# actuatorboard.net
KiCad netlist of a schematic drawn in EAGLE
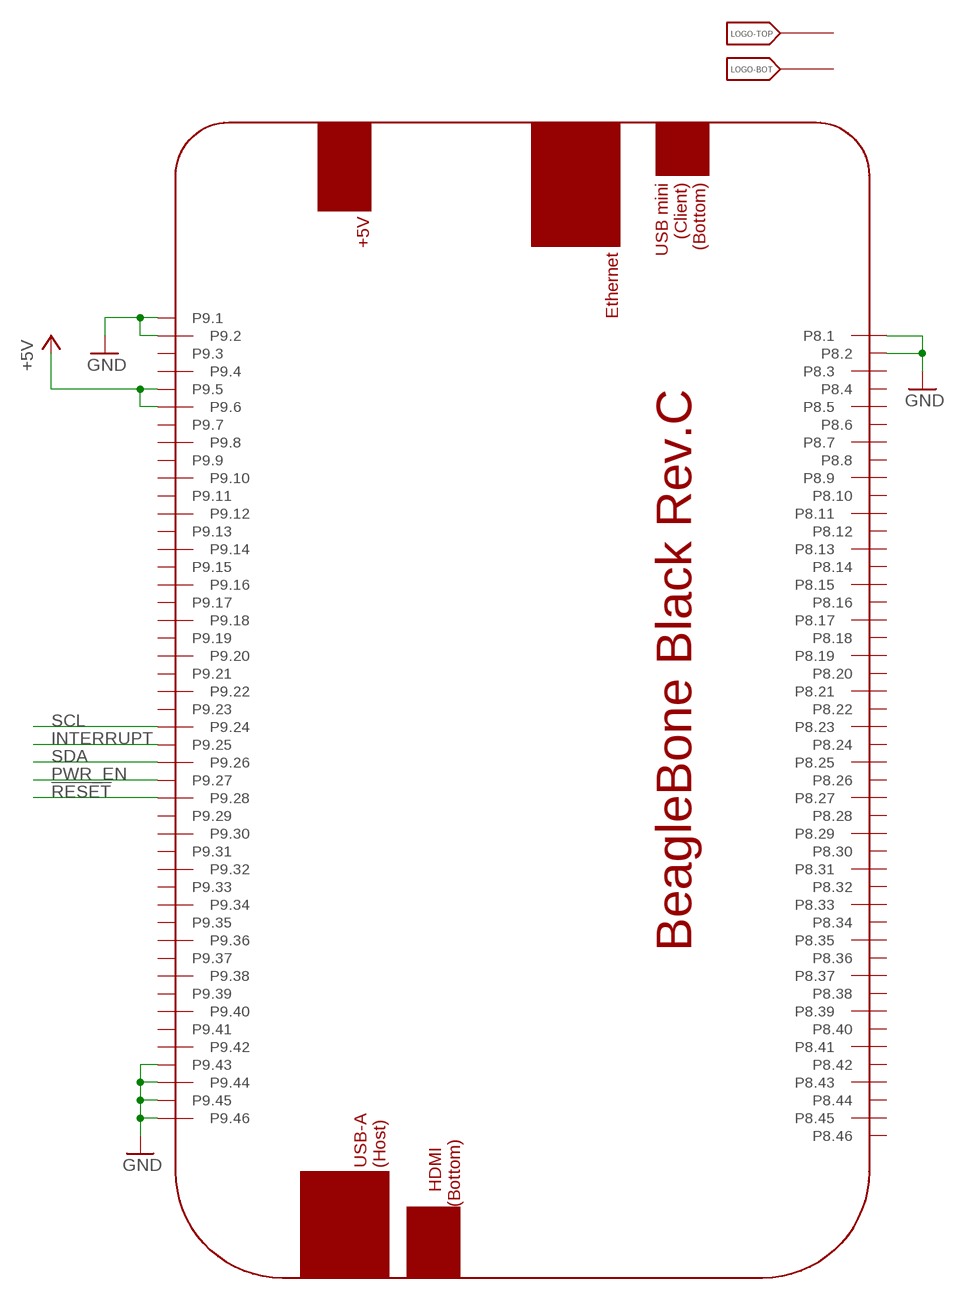
[diagram p0: schematic, sheet 1, part 1 of 2]
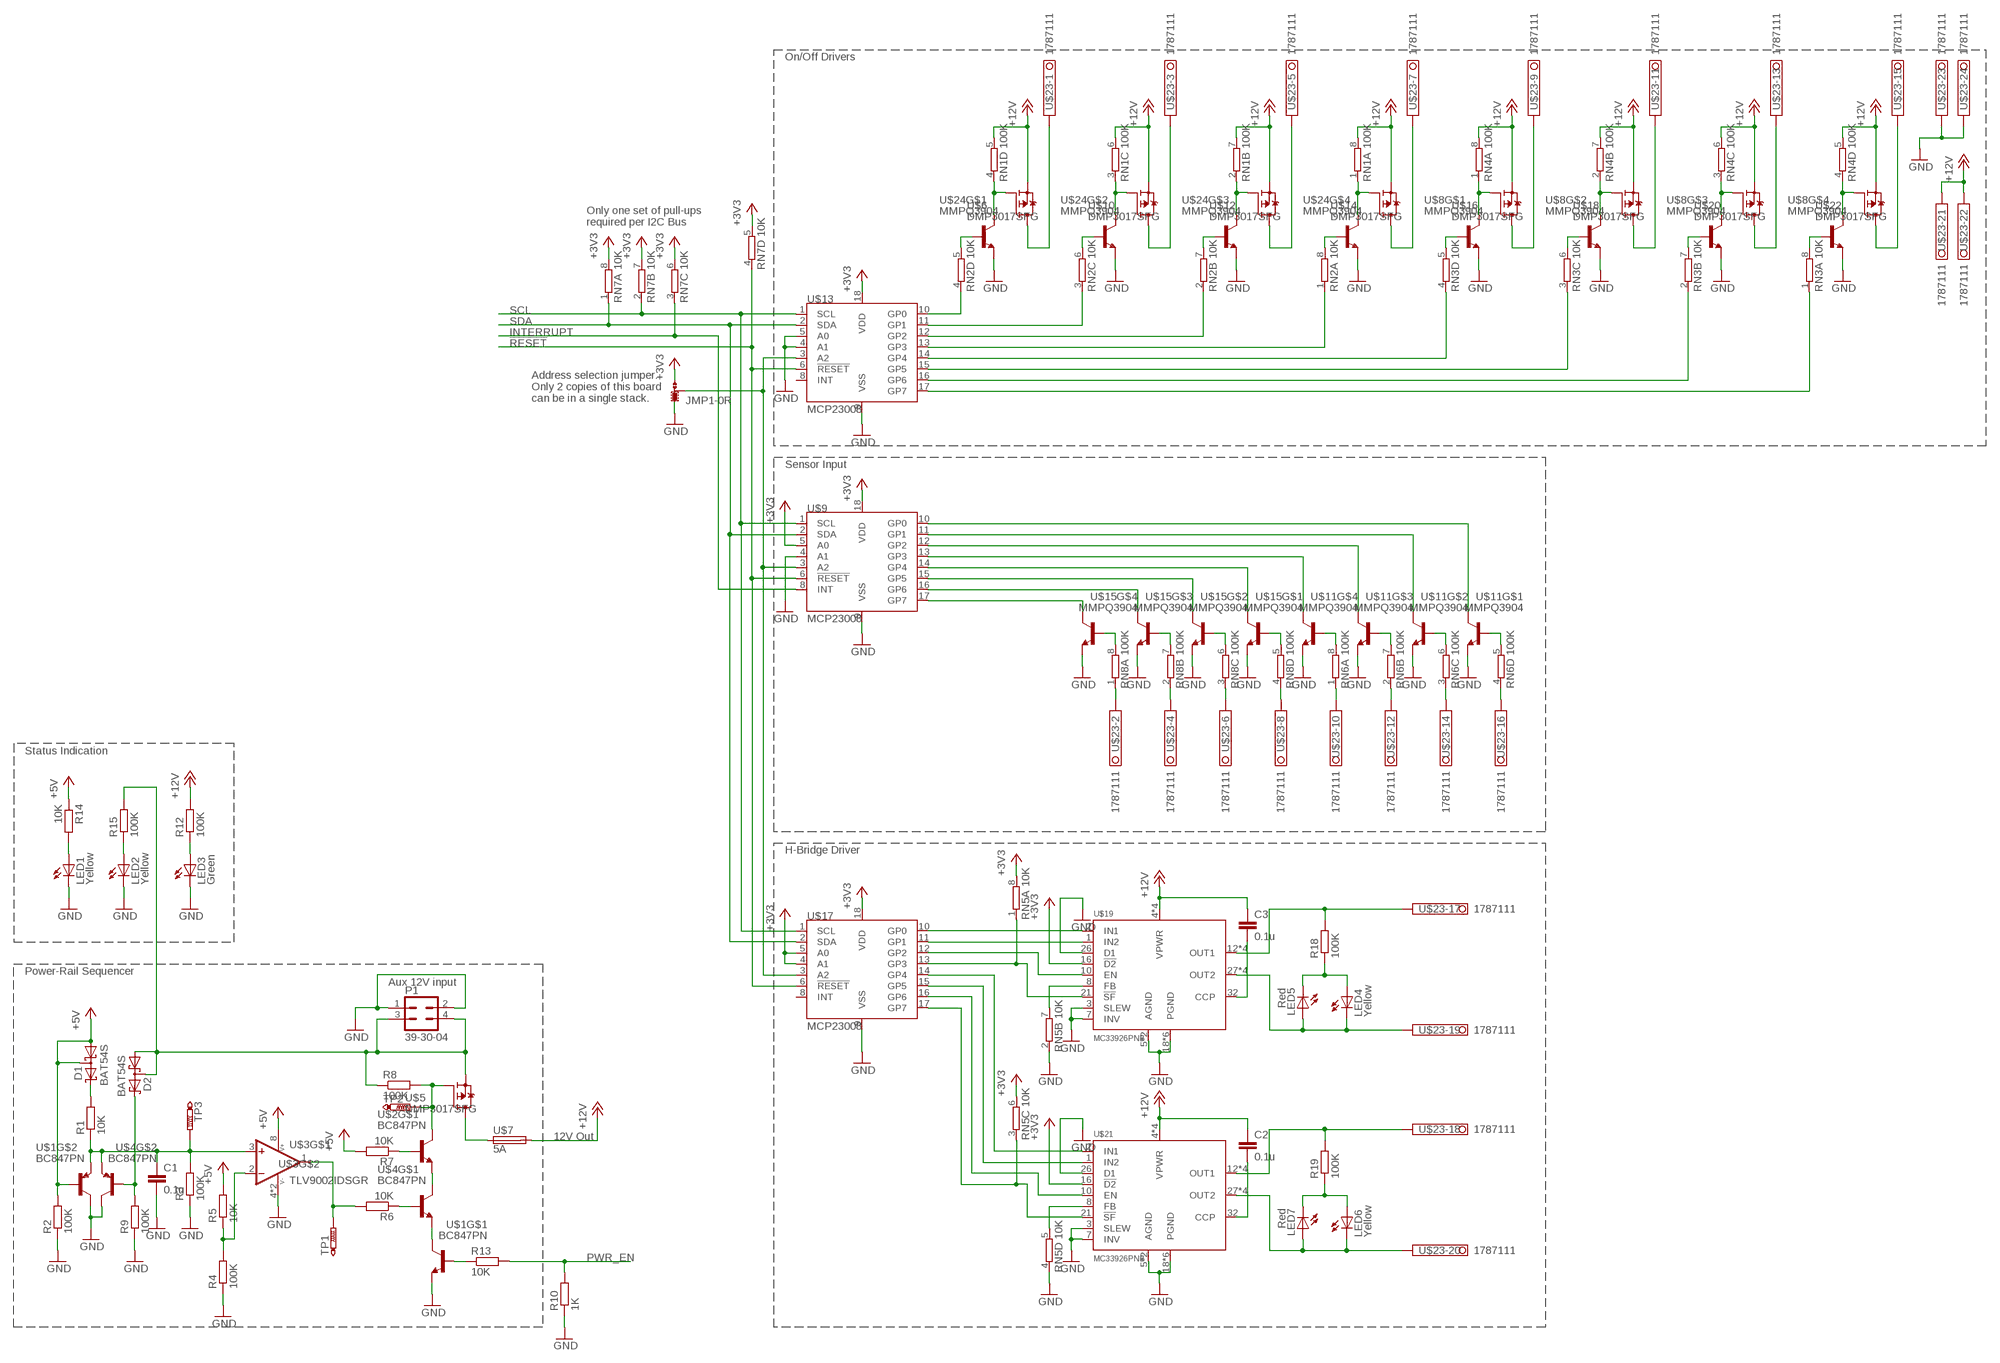
[diagram p1: schematic, sheet 1, part 2 of 2]

(export (version "E")
  (design (tool "Eeschema 10.0.6"))
  (components
    (comp (ref "C1")
      (value "0.1u")
      (footprint "eagle-import:C0805")
      (libsource (lib "eagle-import") (part "C-EUC0805"))
    )
    (comp (ref "C2")
      (value "0.1u")
      (footprint "eagle-import:C0805")
      (libsource (lib "eagle-import") (part "C-EUC0805"))
    )
    (comp (ref "C3")
      (value "0.1u")
      (footprint "eagle-import:C0805")
      (libsource (lib "eagle-import") (part "C-EUC0805"))
    )
    (comp (ref "D1")
      (value "BAT54S")
      (footprint "eagle-import:SOT23")
      (libsource (lib "eagle-import") (part "BAT54S"))
    )
    (comp (ref "D2")
      (value "BAT54S")
      (footprint "eagle-import:SOT23")
      (libsource (lib "eagle-import") (part "BAT54S"))
    )
    (comp (ref "JMP1")
      (value "0R-JUMPA")
      (footprint "eagle-import:A0R-JMP")
      (libsource (lib "eagle-import") (part "0R-JUMPA"))
    )
    (comp (ref "LED1")
      (value "Yellow")
      (footprint "eagle-import:CHIPLED_0805")
      (libsource (lib "eagle-import") (part "LEDCHIPLED_0805"))
    )
    (comp (ref "LED2")
      (value "Yellow")
      (footprint "eagle-import:CHIPLED_0805")
      (libsource (lib "eagle-import") (part "LEDCHIPLED_0805"))
    )
    (comp (ref "LED3")
      (value "Green")
      (footprint "eagle-import:CHIPLED_0805")
      (libsource (lib "eagle-import") (part "LEDCHIPLED_0805"))
    )
    (comp (ref "LED4")
      (value "Yellow")
      (footprint "eagle-import:CHIPLED_0805")
      (libsource (lib "eagle-import") (part "LEDCHIPLED_0805"))
    )
    (comp (ref "LED5")
      (value "Red")
      (footprint "eagle-import:CHIPLED_0805")
      (libsource (lib "eagle-import") (part "LEDCHIPLED_0805"))
    )
    (comp (ref "LED6")
      (value "Yellow")
      (footprint "eagle-import:CHIPLED_0805")
      (libsource (lib "eagle-import") (part "LEDCHIPLED_0805"))
    )
    (comp (ref "LED7")
      (value "Red")
      (footprint "eagle-import:CHIPLED_0805")
      (libsource (lib "eagle-import") (part "LEDCHIPLED_0805"))
    )
    (comp (ref "LOGO")
      (value "SU_LOGO-DUMMY")
      (footprint "eagle-import:SU_LOGO_DS")
      (libsource (lib "eagle-import") (part "SU_LOGO-DUMMY"))
    )
    (comp (ref "P1")
      (value "39-30-04")
      (footprint "eagle-import:39-30-_04_")
      (libsource (lib "eagle-import") (part "39-30-?04?"))
    )
    (comp (ref "PCB1")
      (value "BEAGLEBONE_BLACK_CAPENO_ETH")
      (footprint "eagle-import:BEAGLEBONE_BLACK_CAPE_NO_ETH")
      (libsource (lib "eagle-import") (part "BEAGLEBONE_BLACK_CAPENO_ETH"))
    )
    (comp (ref "R1")
      (value "10K")
      (footprint "eagle-import:R0805")
      (libsource (lib "eagle-import") (part "R-EU_R0805"))
    )
    (comp (ref "R2")
      (value "100K")
      (footprint "eagle-import:R0805")
      (libsource (lib "eagle-import") (part "R-EU_R0805"))
    )
    (comp (ref "R3")
      (value "100K")
      (footprint "eagle-import:R0805")
      (libsource (lib "eagle-import") (part "R-EU_R0805"))
    )
    (comp (ref "R4")
      (value "100K")
      (footprint "eagle-import:R0805")
      (libsource (lib "eagle-import") (part "R-EU_R0805"))
    )
    (comp (ref "R5")
      (value "10K")
      (footprint "eagle-import:R0805")
      (libsource (lib "eagle-import") (part "R-EU_R0805"))
    )
    (comp (ref "R6")
      (value "10K")
      (footprint "eagle-import:R0805")
      (libsource (lib "eagle-import") (part "R-EU_R0805"))
    )
    (comp (ref "R7")
      (value "10K")
      (footprint "eagle-import:R0805")
      (libsource (lib "eagle-import") (part "R-EU_R0805"))
    )
    (comp (ref "R8")
      (value "100K")
      (footprint "eagle-import:R0805")
      (libsource (lib "eagle-import") (part "R-EU_R0805"))
    )
    (comp (ref "R9")
      (value "100K")
      (footprint "eagle-import:R0805")
      (libsource (lib "eagle-import") (part "R-EU_R0805"))
    )
    (comp (ref "R10")
      (value "1K")
      (footprint "eagle-import:R0805")
      (libsource (lib "eagle-import") (part "R-EU_R0805"))
    )
    (comp (ref "R12")
      (value "100K")
      (footprint "eagle-import:R0805")
      (libsource (lib "eagle-import") (part "R-EU_R0805"))
    )
    (comp (ref "R13")
      (value "10K")
      (footprint "eagle-import:R0805")
      (libsource (lib "eagle-import") (part "R-EU_R0805"))
    )
    (comp (ref "R14")
      (value "10K")
      (footprint "eagle-import:R0805")
      (libsource (lib "eagle-import") (part "R-EU_R0805"))
    )
    (comp (ref "R15")
      (value "100K")
      (footprint "eagle-import:R0805")
      (libsource (lib "eagle-import") (part "R-EU_R0805"))
    )
    (comp (ref "R18")
      (value "100K")
      (footprint "eagle-import:R0805")
      (libsource (lib "eagle-import") (part "R-EU_R0805"))
    )
    (comp (ref "R19")
      (value "100K")
      (footprint "eagle-import:R0805")
      (libsource (lib "eagle-import") (part "R-EU_R0805"))
    )
    (comp (ref "RN1")
      (value "100K")
      (footprint "eagle-import:EXBV8V")
      (libsource (lib "eagle-import") (part "4R-NEXBV8V"))
    )
    (comp (ref "RN2")
      (value "10K")
      (footprint "eagle-import:EXBV8V")
      (libsource (lib "eagle-import") (part "4R-NEXBV8V"))
    )
    (comp (ref "RN3")
      (value "10K")
      (footprint "eagle-import:EXBV8V")
      (libsource (lib "eagle-import") (part "4R-NEXBV8V"))
    )
    (comp (ref "RN4")
      (value "100K")
      (footprint "eagle-import:EXBV8V")
      (libsource (lib "eagle-import") (part "4R-NEXBV8V"))
    )
    (comp (ref "RN5")
      (value "10K")
      (footprint "eagle-import:EXBV8V")
      (libsource (lib "eagle-import") (part "4R-NEXBV8V"))
    )
    (comp (ref "RN6")
      (value "100K")
      (footprint "eagle-import:EXBV8V")
      (libsource (lib "eagle-import") (part "4R-NEXBV8V"))
    )
    (comp (ref "RN7")
      (value "10K")
      (footprint "eagle-import:EXBV8V")
      (libsource (lib "eagle-import") (part "4R-NEXBV8V"))
    )
    (comp (ref "RN8")
      (value "100K")
      (footprint "eagle-import:EXBV8V")
      (libsource (lib "eagle-import") (part "4R-NEXBV8V"))
    )
    (comp (ref "TP1")
      (value "PTR1B1,27")
      (footprint "eagle-import:B1,27")
      (libsource (lib "eagle-import") (part "PTR1B1,27"))
    )
    (comp (ref "TP2")
      (value "PTR1B1,27")
      (footprint "eagle-import:B1,27")
      (libsource (lib "eagle-import") (part "PTR1B1,27"))
    )
    (comp (ref "TP3")
      (value "PTR1B1,27")
      (footprint "eagle-import:B1,27")
      (libsource (lib "eagle-import") (part "PTR1B1,27"))
    )
    (comp (ref "U$1")
      (value "BC847PN")
      (footprint "eagle-import:SOT363-INFINION")
      (libsource (lib "eagle-import") (part "BC847PN"))
    )
    (comp (ref "U$2")
      (value "BC847PN")
      (footprint "eagle-import:SOT363-INFINION")
      (libsource (lib "eagle-import") (part "BC847PN"))
    )
    (comp (ref "U$3")
      (value "TLV9002IDSGR")
      (footprint "eagle-import:S-PWSON-N8")
      (libsource (lib "eagle-import") (part "TLV9002IDSGR"))
    )
    (comp (ref "U$4")
      (value "BC847PN")
      (footprint "eagle-import:SOT363-INFINION")
      (libsource (lib "eagle-import") (part "BC847PN"))
    )
    (comp (ref "U$5")
      (value "DMP3017SFG")
      (footprint "eagle-import:POWERDI3333-8")
      (libsource (lib "eagle-import") (part "DMP3017SFG"))
    )
    (comp (ref "U$6")
      (value "DMP3017SFG")
      (footprint "eagle-import:POWERDI3333-8")
      (libsource (lib "eagle-import") (part "DMP3017SFG"))
    )
    (comp (ref "U$7")
      (value "5A")
      (footprint "eagle-import:SMD-1206")
      (libsource (lib "eagle-import") (part "SMD1206"))
    )
    (comp (ref "U$8")
      (value "MMPQ3904")
      (footprint "eagle-import:SOIC-16")
      (libsource (lib "eagle-import") (part "MMPQ3904"))
    )
    (comp (ref "U$9")
      (value "MCP23008")
      (footprint "eagle-import:SO-18W")
      (libsource (lib "eagle-import") (part "MCP23008"))
    )
    (comp (ref "U$10")
      (value "DMP3017SFG")
      (footprint "eagle-import:POWERDI3333-8")
      (libsource (lib "eagle-import") (part "DMP3017SFG"))
    )
    (comp (ref "U$11")
      (value "MMPQ3904")
      (footprint "eagle-import:SOIC-16")
      (libsource (lib "eagle-import") (part "MMPQ3904"))
    )
    (comp (ref "U$12")
      (value "DMP3017SFG")
      (footprint "eagle-import:POWERDI3333-8")
      (libsource (lib "eagle-import") (part "DMP3017SFG"))
    )
    (comp (ref "U$13")
      (value "MCP23008")
      (footprint "eagle-import:SO-18W")
      (libsource (lib "eagle-import") (part "MCP23008"))
    )
    (comp (ref "U$14")
      (value "DMP3017SFG")
      (footprint "eagle-import:POWERDI3333-8")
      (libsource (lib "eagle-import") (part "DMP3017SFG"))
    )
    (comp (ref "U$15")
      (value "MMPQ3904")
      (footprint "eagle-import:SOIC-16")
      (libsource (lib "eagle-import") (part "MMPQ3904"))
    )
    (comp (ref "U$16")
      (value "DMP3017SFG")
      (footprint "eagle-import:POWERDI3333-8")
      (libsource (lib "eagle-import") (part "DMP3017SFG"))
    )
    (comp (ref "U$17")
      (value "MCP23008")
      (footprint "eagle-import:SO-18W")
      (libsource (lib "eagle-import") (part "MCP23008"))
    )
    (comp (ref "U$18")
      (value "DMP3017SFG")
      (footprint "eagle-import:POWERDI3333-8")
      (libsource (lib "eagle-import") (part "DMP3017SFG"))
    )
    (comp (ref "U$19")
      (value "MC33926PNB")
      (footprint "eagle-import:PQFN-32")
      (libsource (lib "eagle-import") (part "MC33926PNB"))
    )
    (comp (ref "U$20")
      (value "DMP3017SFG")
      (footprint "eagle-import:POWERDI3333-8")
      (libsource (lib "eagle-import") (part "DMP3017SFG"))
    )
    (comp (ref "U$21")
      (value "MC33926PNB")
      (footprint "eagle-import:PQFN-32")
      (libsource (lib "eagle-import") (part "MC33926PNB"))
    )
    (comp (ref "U$22")
      (value "DMP3017SFG")
      (footprint "eagle-import:POWERDI3333-8")
      (libsource (lib "eagle-import") (part "DMP3017SFG"))
    )
    (comp (ref "U$23")
      (value "1787111")
      (footprint "eagle-import:1787111")
      (libsource (lib "eagle-import") (part "1787111"))
    )
    (comp (ref "U$24")
      (value "MMPQ3904")
      (footprint "eagle-import:SOIC-16")
      (libsource (lib "eagle-import") (part "MMPQ3904"))
    )
  )
  (nets
    (net (code "1") (name "+3V3") (class "Default")
      (node (ref "JMP1") (pin "3") (pinfunction "3_3") (pintype "passive"))
      (node (ref "RN5") (pin "6") (pinfunction "2_6") (pintype "passive"))
      (node (ref "RN5") (pin "8") (pinfunction "2_8") (pintype "passive"))
      (node (ref "RN7") (pin "5") (pinfunction "2_5") (pintype "passive"))
      (node (ref "RN7") (pin "6") (pinfunction "2_6") (pintype "passive"))
      (node (ref "RN7") (pin "7") (pinfunction "2_7") (pintype "passive"))
      (node (ref "RN7") (pin "8") (pinfunction "2_8") (pintype "passive"))
      (node (ref "U$13") (pin "18") (pinfunction "VDD_18") (pintype "power_in"))
      (node (ref "U$17") (pin "18") (pinfunction "VDD_18") (pintype "power_in"))
      (node (ref "U$17") (pin "4") (pinfunction "A1_4") (pintype "input"))
      (node (ref "U$17") (pin "5") (pinfunction "A0_5") (pintype "input"))
      (node (ref "U$19") (pin "16") (pinfunction "~{D2}_16") (pintype "input"))
      (node (ref "U$21") (pin "16") (pinfunction "~{D2}_16") (pintype "input"))
      (node (ref "U$9") (pin "18") (pinfunction "VDD_18") (pintype "power_in"))
      (node (ref "U$9") (pin "5") (pinfunction "A0_5") (pintype "input"))
    )
    (net (code "2") (name "+5V") (class "Default")
      (node (ref "D1") (pin "1") (pinfunction "A1_1") (pintype "passive"))
      (node (ref "D1") (pin "3") (pinfunction "C1A2_3") (pintype "passive"))
      (node (ref "PCB1") (pin "P9.5") (pinfunction "P9.5_P9.5") (pintype "bidirectional"))
      (node (ref "PCB1") (pin "P9.6") (pinfunction "P9.6_P9.6") (pintype "bidirectional"))
      (node (ref "R14") (pin "1") (pinfunction "1_1") (pintype "passive"))
      (node (ref "R2") (pin "2") (pinfunction "2_2") (pintype "passive"))
      (node (ref "R5") (pin "2") (pinfunction "2_2") (pintype "passive"))
      (node (ref "R7") (pin "2") (pinfunction "2_2") (pintype "passive"))
      (node (ref "U$1") (pin "5") (pinfunction "B_5") (pintype "passive"))
      (node (ref "U$3") (pin "8") (pinfunction "V+_8") (pintype "power_in"))
    )
    (net (code "3") (name "+12V") (class "Default")
      (node (ref "C2") (pin "1") (pinfunction "1_1") (pintype "passive"))
      (node (ref "C3") (pin "1") (pinfunction "1_1") (pintype "passive"))
      (node (ref "R12") (pin "2") (pinfunction "2_2") (pintype "passive"))
      (node (ref "RN1") (pin "5") (pinfunction "2_5") (pintype "passive"))
      (node (ref "RN1") (pin "6") (pinfunction "2_6") (pintype "passive"))
      (node (ref "RN1") (pin "7") (pinfunction "2_7") (pintype "passive"))
      (node (ref "RN1") (pin "8") (pinfunction "2_8") (pintype "passive"))
      (node (ref "RN4") (pin "5") (pinfunction "2_5") (pintype "passive"))
      (node (ref "RN4") (pin "6") (pinfunction "2_6") (pintype "passive"))
      (node (ref "RN4") (pin "7") (pinfunction "2_7") (pintype "passive"))
      (node (ref "RN4") (pin "8") (pinfunction "2_8") (pintype "passive"))
      (node (ref "U$10") (pin "P$1") (pinfunction "S_P$1") (pintype "passive"))
      (node (ref "U$10") (pin "P$2") (pinfunction "S_P$2") (pintype "passive"))
      (node (ref "U$10") (pin "P$3") (pinfunction "S_P$3") (pintype "passive"))
      (node (ref "U$12") (pin "P$1") (pinfunction "S_P$1") (pintype "passive"))
      (node (ref "U$12") (pin "P$2") (pinfunction "S_P$2") (pintype "passive"))
      (node (ref "U$12") (pin "P$3") (pinfunction "S_P$3") (pintype "passive"))
      (node (ref "U$14") (pin "P$1") (pinfunction "S_P$1") (pintype "passive"))
      (node (ref "U$14") (pin "P$2") (pinfunction "S_P$2") (pintype "passive"))
      (node (ref "U$14") (pin "P$3") (pinfunction "S_P$3") (pintype "passive"))
      (node (ref "U$16") (pin "P$1") (pinfunction "S_P$1") (pintype "passive"))
      (node (ref "U$16") (pin "P$2") (pinfunction "S_P$2") (pintype "passive"))
      (node (ref "U$16") (pin "P$3") (pinfunction "S_P$3") (pintype "passive"))
      (node (ref "U$18") (pin "P$1") (pinfunction "S_P$1") (pintype "passive"))
      (node (ref "U$18") (pin "P$2") (pinfunction "S_P$2") (pintype "passive"))
      (node (ref "U$18") (pin "P$3") (pinfunction "S_P$3") (pintype "passive"))
      (node (ref "U$19") (pin "11") (pinfunction "VPWR_11") (pintype "power_in"))
      (node (ref "U$19") (pin "31") (pinfunction "VPWR_31") (pintype "power_in"))
      (node (ref "U$19") (pin "4") (pinfunction "VPWR_4") (pintype "power_in"))
      (node (ref "U$19") (pin "6") (pinfunction "VPWR_6") (pintype "power_in"))
      (node (ref "U$20") (pin "P$1") (pinfunction "S_P$1") (pintype "passive"))
      (node (ref "U$20") (pin "P$2") (pinfunction "S_P$2") (pintype "passive"))
      (node (ref "U$20") (pin "P$3") (pinfunction "S_P$3") (pintype "passive"))
      (node (ref "U$21") (pin "11") (pinfunction "VPWR_11") (pintype "power_in"))
      (node (ref "U$21") (pin "31") (pinfunction "VPWR_31") (pintype "power_in"))
      (node (ref "U$21") (pin "4") (pinfunction "VPWR_4") (pintype "power_in"))
      (node (ref "U$21") (pin "6") (pinfunction "VPWR_6") (pintype "power_in"))
      (node (ref "U$22") (pin "P$1") (pinfunction "S_P$1") (pintype "passive"))
      (node (ref "U$22") (pin "P$2") (pinfunction "S_P$2") (pintype "passive"))
      (node (ref "U$22") (pin "P$3") (pinfunction "S_P$3") (pintype "passive"))
      (node (ref "U$23") (pin "21") (pinfunction "K_21") (pintype "passive"))
      (node (ref "U$23") (pin "22") (pinfunction "K_22") (pintype "passive"))
      (node (ref "U$6") (pin "P$1") (pinfunction "S_P$1") (pintype "passive"))
      (node (ref "U$6") (pin "P$2") (pinfunction "S_P$2") (pintype "passive"))
      (node (ref "U$6") (pin "P$3") (pinfunction "S_P$3") (pintype "passive"))
      (node (ref "U$7") (pin "2") (pinfunction "2_2") (pintype "passive"))
    )
    (net (code "4") (name "/INTERRUPT") (class "Default")
      (node (ref "PCB1") (pin "P9.25") (pinfunction "P9.25_P9.25") (pintype "bidirectional"))
      (node (ref "RN7") (pin "3") (pinfunction "1_3") (pintype "passive"))
      (node (ref "U$9") (pin "8") (pinfunction "INT_8") (pintype "output"))
    )
    (net (code "5") (name "/PWR_EN") (class "Default")
      (node (ref "PCB1") (pin "P9.27") (pinfunction "P9.27_P9.27") (pintype "bidirectional"))
      (node (ref "R10") (pin "2") (pinfunction "2_2") (pintype "passive"))
      (node (ref "R13") (pin "2") (pinfunction "2_2") (pintype "passive"))
    )
    (net (code "6") (name "/SCL") (class "Default")
      (node (ref "PCB1") (pin "P9.24") (pinfunction "P9.24_P9.24") (pintype "bidirectional"))
      (node (ref "RN7") (pin "2") (pinfunction "1_2") (pintype "passive"))
      (node (ref "U$13") (pin "1") (pinfunction "SCL_1") (pintype "input"))
      (node (ref "U$17") (pin "1") (pinfunction "SCL_1") (pintype "input"))
      (node (ref "U$9") (pin "1") (pinfunction "SCL_1") (pintype "input"))
    )
    (net (code "7") (name "/SDA") (class "Default")
      (node (ref "PCB1") (pin "P9.26") (pinfunction "P9.26_P9.26") (pintype "bidirectional"))
      (node (ref "RN7") (pin "1") (pinfunction "1_1") (pintype "passive"))
      (node (ref "U$13") (pin "2") (pinfunction "SDA_2") (pintype "input"))
      (node (ref "U$17") (pin "2") (pinfunction "SDA_2") (pintype "input"))
      (node (ref "U$9") (pin "2") (pinfunction "SDA_2") (pintype "input"))
    )
    (net (code "8") (name "/~{RESET}") (class "Default")
      (node (ref "PCB1") (pin "P9.28") (pinfunction "P9.28_P9.28") (pintype "bidirectional"))
      (node (ref "RN7") (pin "4") (pinfunction "1_4") (pintype "passive"))
      (node (ref "U$13") (pin "6") (pinfunction "~{RESET}_6") (pintype "input"))
      (node (ref "U$17") (pin "6") (pinfunction "~{RESET}_6") (pintype "input"))
      (node (ref "U$9") (pin "6") (pinfunction "~{RESET}_6") (pintype "input"))
    )
    (net (code "9") (name "GND") (class "Default")
      (node (ref "C1") (pin "2") (pinfunction "2_2") (pintype "passive"))
      (node (ref "JMP1") (pin "1") (pinfunction "1_1") (pintype "passive"))
      (node (ref "LED1") (pin "C") (pinfunction "C_C") (pintype "passive"))
      (node (ref "LED2") (pin "C") (pinfunction "C_C") (pintype "passive"))
      (node (ref "LED3") (pin "C") (pinfunction "C_C") (pintype "passive"))
      (node (ref "P1") (pin "1") (pinfunction "1_1") (pintype "passive"))
      (node (ref "P1") (pin "2") (pinfunction "2_2") (pintype "passive"))
      (node (ref "PCB1") (pin "P8.1") (pinfunction "P8.1_P8.1") (pintype "bidirectional"))
      (node (ref "PCB1") (pin "P8.2") (pinfunction "P8.2_P8.2") (pintype "bidirectional"))
      (node (ref "PCB1") (pin "P9.1") (pinfunction "P9.1_P9.1") (pintype "bidirectional"))
      (node (ref "PCB1") (pin "P9.2") (pinfunction "P9.2_P9.2") (pintype "bidirectional"))
      (node (ref "PCB1") (pin "P9.43") (pinfunction "P9.43_P9.43") (pintype "bidirectional"))
      (node (ref "PCB1") (pin "P9.44") (pinfunction "P9.44_P9.44") (pintype "bidirectional"))
      (node (ref "PCB1") (pin "P9.45") (pinfunction "P9.45_P9.45") (pintype "bidirectional"))
      (node (ref "PCB1") (pin "P9.46") (pinfunction "P9.46_P9.46") (pintype "bidirectional"))
      (node (ref "R10") (pin "1") (pinfunction "1_1") (pintype "passive"))
      (node (ref "R2") (pin "1") (pinfunction "1_1") (pintype "passive"))
      (node (ref "R3") (pin "1") (pinfunction "1_1") (pintype "passive"))
      (node (ref "R4") (pin "1") (pinfunction "1_1") (pintype "passive"))
      (node (ref "R9") (pin "1") (pinfunction "1_1") (pintype "passive"))
      (node (ref "RN5") (pin "2") (pinfunction "1_2") (pintype "passive"))
      (node (ref "RN5") (pin "4") (pinfunction "1_4") (pintype "passive"))
      (node (ref "U$1") (pin "1") (pinfunction "E_1") (pintype "passive"))
      (node (ref "U$1") (pin "3") (pinfunction "C_3") (pintype "passive"))
      (node (ref "U$11") (pin "P$10") (pinfunction "E_P$10") (pintype "passive"))
      (node (ref "U$11") (pin "P$12") (pinfunction "E_P$12") (pintype "passive"))
      (node (ref "U$11") (pin "P$14") (pinfunction "E_P$14") (pintype "passive"))
      (node (ref "U$11") (pin "P$16") (pinfunction "E_P$16") (pintype "passive"))
      (node (ref "U$13") (pin "4") (pinfunction "A1_4") (pintype "input"))
      (node (ref "U$13") (pin "5") (pinfunction "A0_5") (pintype "input"))
      (node (ref "U$13") (pin "9") (pinfunction "VSS_9") (pintype "power_in"))
      (node (ref "U$15") (pin "P$10") (pinfunction "E_P$10") (pintype "passive"))
      (node (ref "U$15") (pin "P$12") (pinfunction "E_P$12") (pintype "passive"))
      (node (ref "U$15") (pin "P$14") (pinfunction "E_P$14") (pintype "passive"))
      (node (ref "U$15") (pin "P$16") (pinfunction "E_P$16") (pintype "passive"))
      (node (ref "U$17") (pin "9") (pinfunction "VSS_9") (pintype "power_in"))
      (node (ref "U$19") (pin "18") (pinfunction "PGND_18") (pintype "power_in"))
      (node (ref "U$19") (pin "19") (pinfunction "PGND_19") (pintype "power_in"))
      (node (ref "U$19") (pin "20") (pinfunction "PGND_20") (pintype "power_in"))
      (node (ref "U$19") (pin "22") (pinfunction "PGND_22") (pintype "power_in"))
      (node (ref "U$19") (pin "23") (pinfunction "PGND_23") (pintype "power_in"))
      (node (ref "U$19") (pin "24") (pinfunction "PGND_24") (pintype "power_in"))
      (node (ref "U$19") (pin "26") (pinfunction "D1_26") (pintype "input"))
      (node (ref "U$19") (pin "3") (pinfunction "SLEW_3") (pintype "input"))
      (node (ref "U$19") (pin "5") (pinfunction "AGND_5") (pintype "power_in"))
      (node (ref "U$19") (pin "7") (pinfunction "INV_7") (pintype "input"))
      (node (ref "U$19") (pin "PAD") (pinfunction "AGND_PAD") (pintype "power_in"))
      (node (ref "U$21") (pin "18") (pinfunction "PGND_18") (pintype "power_in"))
      (node (ref "U$21") (pin "19") (pinfunction "PGND_19") (pintype "power_in"))
      (node (ref "U$21") (pin "20") (pinfunction "PGND_20") (pintype "power_in"))
      (node (ref "U$21") (pin "22") (pinfunction "PGND_22") (pintype "power_in"))
      (node (ref "U$21") (pin "23") (pinfunction "PGND_23") (pintype "power_in"))
      (node (ref "U$21") (pin "24") (pinfunction "PGND_24") (pintype "power_in"))
      (node (ref "U$21") (pin "26") (pinfunction "D1_26") (pintype "input"))
      (node (ref "U$21") (pin "3") (pinfunction "SLEW_3") (pintype "input"))
      (node (ref "U$21") (pin "5") (pinfunction "AGND_5") (pintype "power_in"))
      (node (ref "U$21") (pin "7") (pinfunction "INV_7") (pintype "input"))
      (node (ref "U$21") (pin "PAD") (pinfunction "AGND_PAD") (pintype "power_in"))
      (node (ref "U$23") (pin "23") (pinfunction "K_23") (pintype "passive"))
      (node (ref "U$23") (pin "24") (pinfunction "K_24") (pintype "passive"))
      (node (ref "U$24") (pin "P$10") (pinfunction "E_P$10") (pintype "passive"))
      (node (ref "U$24") (pin "P$12") (pinfunction "E_P$12") (pintype "passive"))
      (node (ref "U$24") (pin "P$14") (pinfunction "E_P$14") (pintype "passive"))
      (node (ref "U$24") (pin "P$16") (pinfunction "E_P$16") (pintype "passive"))
      (node (ref "U$3") (pin "4") (pinfunction "V-_4") (pintype "power_in"))
      (node (ref "U$3") (pin "PAD") (pinfunction "V-_PAD") (pintype "power_in"))
      (node (ref "U$4") (pin "3") (pinfunction "C_3") (pintype "passive"))
      (node (ref "U$8") (pin "P$10") (pinfunction "E_P$10") (pintype "passive"))
      (node (ref "U$8") (pin "P$12") (pinfunction "E_P$12") (pintype "passive"))
      (node (ref "U$8") (pin "P$14") (pinfunction "E_P$14") (pintype "passive"))
      (node (ref "U$8") (pin "P$16") (pinfunction "E_P$16") (pintype "passive"))
      (node (ref "U$9") (pin "4") (pinfunction "A1_4") (pintype "input"))
      (node (ref "U$9") (pin "9") (pinfunction "VSS_9") (pintype "power_in"))
    )
    (net (code "10") (name "Net-(D1-C2)") (class "Default")
      (node (ref "D1") (pin "2") (pinfunction "C2_2") (pintype "passive"))
      (node (ref "R1") (pin "2") (pinfunction "2_2") (pintype "passive"))
    )
    (net (code "11") (name "Net-(D2-A1)") (class "Default")
      (node (ref "D2") (pin "1") (pinfunction "A1_1") (pintype "passive"))
      (node (ref "D2") (pin "3") (pinfunction "C1A2_3") (pintype "passive"))
      (node (ref "P1") (pin "3") (pinfunction "3_3") (pintype "passive"))
      (node (ref "P1") (pin "4") (pinfunction "4_4") (pintype "passive"))
      (node (ref "R15") (pin "2") (pinfunction "2_2") (pintype "passive"))
      (node (ref "R8") (pin "1") (pinfunction "1_1") (pintype "passive"))
      (node (ref "U$5") (pin "P$1") (pinfunction "S_P$1") (pintype "passive"))
      (node (ref "U$5") (pin "P$2") (pinfunction "S_P$2") (pintype "passive"))
      (node (ref "U$5") (pin "P$3") (pinfunction "S_P$3") (pintype "passive"))
    )
    (net (code "12") (name "Net-(D2-C2)") (class "Default")
      (node (ref "D2") (pin "2") (pinfunction "C2_2") (pintype "passive"))
      (node (ref "R9") (pin "2") (pinfunction "2_2") (pintype "passive"))
      (node (ref "U$4") (pin "5") (pinfunction "B_5") (pintype "passive"))
    )
    (net (code "13") (name "Net-(LED1-PadA)") (class "Default")
      (node (ref "LED1") (pin "A") (pinfunction "A_A") (pintype "passive"))
      (node (ref "R14") (pin "2") (pinfunction "2_2") (pintype "passive"))
    )
    (net (code "14") (name "Net-(LED2-PadA)") (class "Default")
      (node (ref "LED2") (pin "A") (pinfunction "A_A") (pintype "passive"))
      (node (ref "R15") (pin "1") (pinfunction "1_1") (pintype "passive"))
    )
    (net (code "15") (name "Net-(LED3-PadA)") (class "Default")
      (node (ref "LED3") (pin "A") (pinfunction "A_A") (pintype "passive"))
      (node (ref "R12") (pin "1") (pinfunction "1_1") (pintype "passive"))
    )
    (net (code "16") (name "Net-(LED4-PadA)") (class "Default")
      (node (ref "LED4") (pin "A") (pinfunction "A_A") (pintype "passive"))
      (node (ref "LED5") (pin "C") (pinfunction "C_C") (pintype "passive"))
      (node (ref "R18") (pin "1") (pinfunction "1_1") (pintype "passive"))
    )
    (net (code "17") (name "Net-(LED6-PadA)") (class "Default")
      (node (ref "LED6") (pin "A") (pinfunction "A_A") (pintype "passive"))
      (node (ref "LED7") (pin "C") (pinfunction "C_C") (pintype "passive"))
      (node (ref "R19") (pin "1") (pinfunction "1_1") (pintype "passive"))
    )
    (net (code "18") (name "Net-(RN1B-1)") (class "Default")
      (node (ref "RN1") (pin "2") (pinfunction "1_2") (pintype "passive"))
      (node (ref "U$12") (pin "P$4") (pinfunction "G_P$4") (pintype "passive"))
      (node (ref "U$24") (pin "P$5") (pinfunction "C_P$5") (pintype "passive"))
      (node (ref "U$24") (pin "P$6") (pinfunction "C_P$6") (pintype "passive"))
    )
    (net (code "19") (name "Net-(RN1C-1)") (class "Default")
      (node (ref "RN1") (pin "3") (pinfunction "1_3") (pintype "passive"))
      (node (ref "U$10") (pin "P$4") (pinfunction "G_P$4") (pintype "passive"))
      (node (ref "U$24") (pin "P$3") (pinfunction "C_P$3") (pintype "passive"))
      (node (ref "U$24") (pin "P$4") (pinfunction "C_P$4") (pintype "passive"))
    )
    (net (code "20") (name "Net-(RN1D-1)") (class "Default")
      (node (ref "RN1") (pin "4") (pinfunction "1_4") (pintype "passive"))
      (node (ref "U$24") (pin "P$1") (pinfunction "C_P$1") (pintype "passive"))
      (node (ref "U$24") (pin "P$2") (pinfunction "C_P$2") (pintype "passive"))
      (node (ref "U$6") (pin "P$4") (pinfunction "G_P$4") (pintype "passive"))
    )
    (net (code "21") (name "Net-(RN2A-2)") (class "Default")
      (node (ref "RN2") (pin "8") (pinfunction "2_8") (pintype "passive"))
      (node (ref "U$24") (pin "P$9") (pinfunction "B_P$9") (pintype "passive"))
    )
    (net (code "22") (name "Net-(RN2B-1)") (class "Default")
      (node (ref "RN2") (pin "2") (pinfunction "1_2") (pintype "passive"))
      (node (ref "U$13") (pin "12") (pinfunction "GP2_12") (pintype "bidirectional"))
    )
    (net (code "23") (name "Net-(RN2B-2)") (class "Default")
      (node (ref "RN2") (pin "7") (pinfunction "2_7") (pintype "passive"))
      (node (ref "U$24") (pin "P$11") (pinfunction "B_P$11") (pintype "passive"))
    )
    (net (code "24") (name "Net-(RN2C-1)") (class "Default")
      (node (ref "RN2") (pin "3") (pinfunction "1_3") (pintype "passive"))
      (node (ref "U$13") (pin "11") (pinfunction "GP1_11") (pintype "bidirectional"))
    )
    (net (code "25") (name "Net-(RN2C-2)") (class "Default")
      (node (ref "RN2") (pin "6") (pinfunction "2_6") (pintype "passive"))
      (node (ref "U$24") (pin "P$13") (pinfunction "B_P$13") (pintype "passive"))
    )
    (net (code "26") (name "Net-(RN2D-1)") (class "Default")
      (node (ref "RN2") (pin "4") (pinfunction "1_4") (pintype "passive"))
      (node (ref "U$13") (pin "10") (pinfunction "GP0_10") (pintype "bidirectional"))
    )
    (net (code "27") (name "Net-(RN2D-2)") (class "Default")
      (node (ref "RN2") (pin "5") (pinfunction "2_5") (pintype "passive"))
      (node (ref "U$24") (pin "P$15") (pinfunction "B_P$15") (pintype "passive"))
    )
    (net (code "28") (name "Net-(RN3A-2)") (class "Default")
      (node (ref "RN3") (pin "8") (pinfunction "2_8") (pintype "passive"))
      (node (ref "U$8") (pin "P$9") (pinfunction "B_P$9") (pintype "passive"))
    )
    (net (code "29") (name "Net-(RN3B-1)") (class "Default")
      (node (ref "RN3") (pin "2") (pinfunction "1_2") (pintype "passive"))
      (node (ref "U$13") (pin "16") (pinfunction "GP6_16") (pintype "bidirectional"))
    )
    (net (code "30") (name "Net-(RN3B-2)") (class "Default")
      (node (ref "RN3") (pin "7") (pinfunction "2_7") (pintype "passive"))
      (node (ref "U$8") (pin "P$11") (pinfunction "B_P$11") (pintype "passive"))
    )
    (net (code "31") (name "Net-(RN3C-1)") (class "Default")
      (node (ref "RN3") (pin "3") (pinfunction "1_3") (pintype "passive"))
      (node (ref "U$13") (pin "15") (pinfunction "GP5_15") (pintype "bidirectional"))
    )
    (net (code "32") (name "Net-(RN3C-2)") (class "Default")
      (node (ref "RN3") (pin "6") (pinfunction "2_6") (pintype "passive"))
      (node (ref "U$8") (pin "P$13") (pinfunction "B_P$13") (pintype "passive"))
    )
    (net (code "33") (name "Net-(RN3D-1)") (class "Default")
      (node (ref "RN3") (pin "4") (pinfunction "1_4") (pintype "passive"))
      (node (ref "U$13") (pin "14") (pinfunction "GP4_14") (pintype "bidirectional"))
    )
    (net (code "34") (name "Net-(RN3D-2)") (class "Default")
      (node (ref "RN3") (pin "5") (pinfunction "2_5") (pintype "passive"))
      (node (ref "U$8") (pin "P$15") (pinfunction "B_P$15") (pintype "passive"))
    )
    (net (code "35") (name "Net-(RN4B-1)") (class "Default")
      (node (ref "RN4") (pin "2") (pinfunction "1_2") (pintype "passive"))
      (node (ref "U$18") (pin "P$4") (pinfunction "G_P$4") (pintype "passive"))
      (node (ref "U$8") (pin "P$3") (pinfunction "C_P$3") (pintype "passive"))
      (node (ref "U$8") (pin "P$4") (pinfunction "C_P$4") (pintype "passive"))
    )
    (net (code "36") (name "Net-(RN4C-1)") (class "Default")
      (node (ref "RN4") (pin "3") (pinfunction "1_3") (pintype "passive"))
      (node (ref "U$20") (pin "P$4") (pinfunction "G_P$4") (pintype "passive"))
      (node (ref "U$8") (pin "P$5") (pinfunction "C_P$5") (pintype "passive"))
      (node (ref "U$8") (pin "P$6") (pinfunction "C_P$6") (pintype "passive"))
    )
    (net (code "37") (name "Net-(RN4D-1)") (class "Default")
      (node (ref "RN4") (pin "4") (pinfunction "1_4") (pintype "passive"))
      (node (ref "U$22") (pin "P$4") (pinfunction "G_P$4") (pintype "passive"))
      (node (ref "U$8") (pin "P$7") (pinfunction "C_P$7") (pintype "passive"))
      (node (ref "U$8") (pin "P$8") (pinfunction "C_P$8") (pintype "passive"))
    )
    (net (code "38") (name "Net-(RN5B-2)") (class "Default")
      (node (ref "RN5") (pin "7") (pinfunction "2_7") (pintype "passive"))
      (node (ref "U$19") (pin "8") (pinfunction "FB_8") (pintype "output"))
    )
    (net (code "39") (name "Net-(RN5C-1)") (class "Default")
      (node (ref "RN5") (pin "3") (pinfunction "1_3") (pintype "passive"))
      (node (ref "U$17") (pin "17") (pinfunction "GP7_17") (pintype "bidirectional"))
      (node (ref "U$21") (pin "21") (pinfunction "~{SF}_21") (pintype "output"))
    )
    (net (code "40") (name "Net-(RN5D-2)") (class "Default")
      (node (ref "RN5") (pin "5") (pinfunction "2_5") (pintype "passive"))
      (node (ref "U$21") (pin "8") (pinfunction "FB_8") (pintype "output"))
    )
    (net (code "41") (name "Net-(RN6A-2)") (class "Default")
      (node (ref "RN6") (pin "8") (pinfunction "2_8") (pintype "passive"))
      (node (ref "U$11") (pin "P$9") (pinfunction "B_P$9") (pintype "passive"))
    )
    (net (code "42") (name "Net-(RN6B-1)") (class "Default")
      (node (ref "RN6") (pin "2") (pinfunction "1_2") (pintype "passive"))
      (node (ref "U$23") (pin "12") (pinfunction "K_12") (pintype "passive"))
    )
    (net (code "43") (name "Net-(RN6B-2)") (class "Default")
      (node (ref "RN6") (pin "7") (pinfunction "2_7") (pintype "passive"))
      (node (ref "U$11") (pin "P$11") (pinfunction "B_P$11") (pintype "passive"))
    )
    (net (code "44") (name "Net-(RN6C-1)") (class "Default")
      (node (ref "RN6") (pin "3") (pinfunction "1_3") (pintype "passive"))
      (node (ref "U$23") (pin "14") (pinfunction "K_14") (pintype "passive"))
    )
    (net (code "45") (name "Net-(RN6C-2)") (class "Default")
      (node (ref "RN6") (pin "6") (pinfunction "2_6") (pintype "passive"))
      (node (ref "U$11") (pin "P$13") (pinfunction "B_P$13") (pintype "passive"))
    )
    (net (code "46") (name "Net-(RN6D-1)") (class "Default")
      (node (ref "RN6") (pin "4") (pinfunction "1_4") (pintype "passive"))
      (node (ref "U$23") (pin "16") (pinfunction "K_16") (pintype "passive"))
    )
    (net (code "47") (name "Net-(RN6D-2)") (class "Default")
      (node (ref "RN6") (pin "5") (pinfunction "2_5") (pintype "passive"))
      (node (ref "U$11") (pin "P$15") (pinfunction "B_P$15") (pintype "passive"))
    )
    (net (code "48") (name "Net-(RN8A-2)") (class "Default")
      (node (ref "RN8") (pin "8") (pinfunction "2_8") (pintype "passive"))
      (node (ref "U$15") (pin "P$9") (pinfunction "B_P$9") (pintype "passive"))
    )
    (net (code "49") (name "Net-(RN8B-1)") (class "Default")
      (node (ref "RN8") (pin "2") (pinfunction "1_2") (pintype "passive"))
      (node (ref "U$23") (pin "4") (pinfunction "K_4") (pintype "passive"))
    )
    (net (code "50") (name "Net-(RN8B-2)") (class "Default")
      (node (ref "RN8") (pin "7") (pinfunction "2_7") (pintype "passive"))
      (node (ref "U$15") (pin "P$11") (pinfunction "B_P$11") (pintype "passive"))
    )
    (net (code "51") (name "Net-(RN8C-1)") (class "Default")
      (node (ref "RN8") (pin "3") (pinfunction "1_3") (pintype "passive"))
      (node (ref "U$23") (pin "6") (pinfunction "K_6") (pintype "passive"))
    )
    (net (code "52") (name "Net-(RN8C-2)") (class "Default")
      (node (ref "RN8") (pin "6") (pinfunction "2_6") (pintype "passive"))
      (node (ref "U$15") (pin "P$13") (pinfunction "B_P$13") (pintype "passive"))
    )
    (net (code "53") (name "Net-(RN8D-1)") (class "Default")
      (node (ref "RN8") (pin "4") (pinfunction "1_4") (pintype "passive"))
      (node (ref "U$23") (pin "8") (pinfunction "K_8") (pintype "passive"))
    )
    (net (code "54") (name "Net-(RN8D-2)") (class "Default")
      (node (ref "RN8") (pin "5") (pinfunction "2_5") (pintype "passive"))
      (node (ref "U$15") (pin "P$15") (pinfunction "B_P$15") (pintype "passive"))
    )
    (net (code "55") (name "Net-(U$1A-B)") (class "Default")
      (node (ref "R13") (pin "1") (pinfunction "1_1") (pintype "passive"))
      (node (ref "U$1") (pin "2") (pinfunction "B_2") (pintype "passive"))
    )
    (net (code "56") (name "Net-(U$1A-C)") (class "Default")
      (node (ref "U$1") (pin "6") (pinfunction "C_6") (pintype "passive"))
      (node (ref "U$4") (pin "1") (pinfunction "E_1") (pintype "passive"))
    )
    (net (code "57") (name "Net-(U$1B-E)") (class "Default")
      (node (ref "C1") (pin "1") (pinfunction "1_1") (pintype "passive"))
      (node (ref "R1") (pin "1") (pinfunction "1_1") (pintype "passive"))
      (node (ref "R3") (pin "2") (pinfunction "2_2") (pintype "passive"))
      (node (ref "TP3") (pin "TP") (pinfunction "TP_TP") (pintype "input"))
      (node (ref "U$1") (pin "4") (pinfunction "E_4") (pintype "passive"))
      (node (ref "U$3") (pin "3") (pinfunction "+IN_3") (pintype "input"))
      (node (ref "U$4") (pin "4") (pinfunction "E_4") (pintype "passive"))
    )
    (net (code "58") (name "Net-(U$2A-B)") (class "Default")
      (node (ref "R7") (pin "1") (pinfunction "1_1") (pintype "passive"))
      (node (ref "U$2") (pin "2") (pinfunction "B_2") (pintype "passive"))
    )
    (net (code "59") (name "Net-(U$2A-C)") (class "Default")
      (node (ref "R8") (pin "2") (pinfunction "2_2") (pintype "passive"))
      (node (ref "TP2") (pin "TP") (pinfunction "TP_TP") (pintype "input"))
      (node (ref "U$2") (pin "6") (pinfunction "C_6") (pintype "passive"))
      (node (ref "U$5") (pin "P$4") (pinfunction "G_P$4") (pintype "passive"))
    )
    (net (code "60") (name "Net-(U$2A-E)") (class "Default")
      (node (ref "U$2") (pin "1") (pinfunction "E_1") (pintype "passive"))
      (node (ref "U$4") (pin "6") (pinfunction "C_6") (pintype "passive"))
    )
    (net (code "61") (name "Net-(U$3A--IN)") (class "Default")
      (node (ref "R4") (pin "2") (pinfunction "2_2") (pintype "passive"))
      (node (ref "R5") (pin "1") (pinfunction "1_1") (pintype "passive"))
      (node (ref "U$3") (pin "2") (pinfunction "-IN_2") (pintype "input"))
    )
    (net (code "62") (name "Net-(U$3A-OUT)") (class "Default")
      (node (ref "R6") (pin "2") (pinfunction "2_2") (pintype "passive"))
      (node (ref "TP1") (pin "TP") (pinfunction "TP_TP") (pintype "input"))
      (node (ref "U$3") (pin "1") (pinfunction "OUT_1") (pintype "output"))
    )
    (net (code "63") (name "Net-(U$4A-B)") (class "Default")
      (node (ref "R6") (pin "1") (pinfunction "1_1") (pintype "passive"))
      (node (ref "U$4") (pin "2") (pinfunction "B_2") (pintype "passive"))
    )
    (net (code "64") (name "Net-(U$5-D-PadP$5)") (class "Default")
      (node (ref "U$5") (pin "P$5") (pinfunction "D_P$5") (pintype "passive"))
      (node (ref "U$5") (pin "P$6") (pinfunction "D_P$6") (pintype "passive"))
      (node (ref "U$5") (pin "P$7") (pinfunction "D_P$7") (pintype "passive"))
      (node (ref "U$5") (pin "P$8") (pinfunction "D_P$8") (pintype "passive"))
      (node (ref "U$7") (pin "1") (pinfunction "1_1") (pintype "passive"))
    )
    (net (code "65") (name "Net-(U$9-GP0)") (class "Default")
      (node (ref "U$11") (pin "P$1") (pinfunction "C_P$1") (pintype "passive"))
      (node (ref "U$11") (pin "P$2") (pinfunction "C_P$2") (pintype "passive"))
      (node (ref "U$9") (pin "10") (pinfunction "GP0_10") (pintype "bidirectional"))
    )
    (net (code "66") (name "Net-(U$9-GP1)") (class "Default")
      (node (ref "U$11") (pin "P$3") (pinfunction "C_P$3") (pintype "passive"))
      (node (ref "U$11") (pin "P$4") (pinfunction "C_P$4") (pintype "passive"))
      (node (ref "U$9") (pin "11") (pinfunction "GP1_11") (pintype "bidirectional"))
    )
    (net (code "67") (name "Net-(U$9-GP2)") (class "Default")
      (node (ref "U$11") (pin "P$5") (pinfunction "C_P$5") (pintype "passive"))
      (node (ref "U$11") (pin "P$6") (pinfunction "C_P$6") (pintype "passive"))
      (node (ref "U$9") (pin "12") (pinfunction "GP2_12") (pintype "bidirectional"))
    )
    (net (code "68") (name "Net-(U$9-GP3)") (class "Default")
      (node (ref "U$11") (pin "P$7") (pinfunction "C_P$7") (pintype "passive"))
      (node (ref "U$11") (pin "P$8") (pinfunction "C_P$8") (pintype "passive"))
      (node (ref "U$9") (pin "13") (pinfunction "GP3_13") (pintype "bidirectional"))
    )
    (net (code "69") (name "Net-(U$9-GP4)") (class "Default")
      (node (ref "U$15") (pin "P$1") (pinfunction "C_P$1") (pintype "passive"))
      (node (ref "U$15") (pin "P$2") (pinfunction "C_P$2") (pintype "passive"))
      (node (ref "U$9") (pin "14") (pinfunction "GP4_14") (pintype "bidirectional"))
    )
    (net (code "70") (name "Net-(U$9-GP5)") (class "Default")
      (node (ref "U$15") (pin "P$3") (pinfunction "C_P$3") (pintype "passive"))
      (node (ref "U$15") (pin "P$4") (pinfunction "C_P$4") (pintype "passive"))
      (node (ref "U$9") (pin "15") (pinfunction "GP5_15") (pintype "bidirectional"))
    )
    (net (code "71") (name "Net-(U$9-GP6)") (class "Default")
      (node (ref "U$15") (pin "P$5") (pinfunction "C_P$5") (pintype "passive"))
      (node (ref "U$15") (pin "P$6") (pinfunction "C_P$6") (pintype "passive"))
      (node (ref "U$9") (pin "16") (pinfunction "GP6_16") (pintype "bidirectional"))
    )
    (net (code "72") (name "Net-(U$9-GP7)") (class "Default")
      (node (ref "U$15") (pin "P$7") (pinfunction "C_P$7") (pintype "passive"))
      (node (ref "U$15") (pin "P$8") (pinfunction "C_P$8") (pintype "passive"))
      (node (ref "U$9") (pin "17") (pinfunction "GP7_17") (pintype "bidirectional"))
    )
    (net (code "73") (name "Net-(U$13-A2)") (class "Default")
      (node (ref "JMP1") (pin "2") (pinfunction "2_2") (pintype "passive"))
      (node (ref "U$13") (pin "3") (pinfunction "A2_3") (pintype "input"))
      (node (ref "U$17") (pin "3") (pinfunction "A2_3") (pintype "input"))
      (node (ref "U$9") (pin "3") (pinfunction "A2_3") (pintype "input"))
    )
    (net (code "74") (name "Net-(U$13-GP3)") (class "Default")
      (node (ref "RN2") (pin "1") (pinfunction "1_1") (pintype "passive"))
      (node (ref "U$13") (pin "13") (pinfunction "GP3_13") (pintype "bidirectional"))
    )
    (net (code "75") (name "Net-(U$13-GP7)") (class "Default")
      (node (ref "RN3") (pin "1") (pinfunction "1_1") (pintype "passive"))
      (node (ref "U$13") (pin "17") (pinfunction "GP7_17") (pintype "bidirectional"))
    )
    (net (code "76") (name "Net-(U$14-G)") (class "Default")
      (node (ref "RN1") (pin "1") (pinfunction "1_1") (pintype "passive"))
      (node (ref "U$14") (pin "P$4") (pinfunction "G_P$4") (pintype "passive"))
      (node (ref "U$24") (pin "P$7") (pinfunction "C_P$7") (pintype "passive"))
      (node (ref "U$24") (pin "P$8") (pinfunction "C_P$8") (pintype "passive"))
    )
    (net (code "77") (name "Net-(U$16-G)") (class "Default")
      (node (ref "RN4") (pin "1") (pinfunction "1_1") (pintype "passive"))
      (node (ref "U$16") (pin "P$4") (pinfunction "G_P$4") (pintype "passive"))
      (node (ref "U$8") (pin "P$1") (pinfunction "C_P$1") (pintype "passive"))
      (node (ref "U$8") (pin "P$2") (pinfunction "C_P$2") (pintype "passive"))
    )
    (net (code "78") (name "Net-(U$17-GP0)") (class "Default")
      (node (ref "U$17") (pin "10") (pinfunction "GP0_10") (pintype "bidirectional"))
      (node (ref "U$19") (pin "2") (pinfunction "IN1_2") (pintype "input"))
    )
    (net (code "79") (name "Net-(U$17-GP1)") (class "Default")
      (node (ref "U$17") (pin "11") (pinfunction "GP1_11") (pintype "bidirectional"))
      (node (ref "U$19") (pin "1") (pinfunction "IN2_1") (pintype "input"))
    )
    (net (code "80") (name "Net-(U$17-GP2)") (class "Default")
      (node (ref "U$17") (pin "12") (pinfunction "GP2_12") (pintype "bidirectional"))
      (node (ref "U$19") (pin "10") (pinfunction "EN_10") (pintype "input"))
    )
    (net (code "81") (name "Net-(U$17-GP3)") (class "Default")
      (node (ref "RN5") (pin "1") (pinfunction "1_1") (pintype "passive"))
      (node (ref "U$17") (pin "13") (pinfunction "GP3_13") (pintype "bidirectional"))
      (node (ref "U$19") (pin "21") (pinfunction "~{SF}_21") (pintype "output"))
    )
    (net (code "82") (name "Net-(U$17-GP4)") (class "Default")
      (node (ref "U$17") (pin "14") (pinfunction "GP4_14") (pintype "bidirectional"))
      (node (ref "U$21") (pin "2") (pinfunction "IN1_2") (pintype "input"))
    )
    (net (code "83") (name "Net-(U$17-GP5)") (class "Default")
      (node (ref "U$17") (pin "15") (pinfunction "GP5_15") (pintype "bidirectional"))
      (node (ref "U$21") (pin "1") (pinfunction "IN2_1") (pintype "input"))
    )
    (net (code "84") (name "Net-(U$17-GP6)") (class "Default")
      (node (ref "U$17") (pin "16") (pinfunction "GP6_16") (pintype "bidirectional"))
      (node (ref "U$21") (pin "10") (pinfunction "EN_10") (pintype "input"))
    )
    (net (code "85") (name "Net-(U$19-CCP)") (class "Default")
      (node (ref "C3") (pin "2") (pinfunction "2_2") (pintype "passive"))
      (node (ref "U$19") (pin "32") (pinfunction "CCP_32") (pintype "output"))
    )
    (net (code "86") (name "Net-(U$21-CCP)") (class "Default")
      (node (ref "C2") (pin "2") (pinfunction "2_2") (pintype "passive"))
      (node (ref "U$21") (pin "32") (pinfunction "CCP_32") (pintype "output"))
    )
    (net (code "87") (name "Net-(U$23A-K)") (class "Default")
      (node (ref "U$23") (pin "1") (pinfunction "K_1") (pintype "passive"))
      (node (ref "U$6") (pin "P$5") (pinfunction "D_P$5") (pintype "passive"))
      (node (ref "U$6") (pin "P$6") (pinfunction "D_P$6") (pintype "passive"))
      (node (ref "U$6") (pin "P$7") (pinfunction "D_P$7") (pintype "passive"))
      (node (ref "U$6") (pin "P$8") (pinfunction "D_P$8") (pintype "passive"))
    )
    (net (code "88") (name "Net-(U$23B-K)") (class "Default")
      (node (ref "RN6") (pin "1") (pinfunction "1_1") (pintype "passive"))
      (node (ref "U$23") (pin "10") (pinfunction "K_10") (pintype "passive"))
    )
    (net (code "89") (name "Net-(U$23C-K)") (class "Default")
      (node (ref "U$18") (pin "P$5") (pinfunction "D_P$5") (pintype "passive"))
      (node (ref "U$18") (pin "P$6") (pinfunction "D_P$6") (pintype "passive"))
      (node (ref "U$18") (pin "P$7") (pinfunction "D_P$7") (pintype "passive"))
      (node (ref "U$18") (pin "P$8") (pinfunction "D_P$8") (pintype "passive"))
      (node (ref "U$23") (pin "11") (pinfunction "K_11") (pintype "passive"))
    )
    (net (code "90") (name "Net-(U$23E-K)") (class "Default")
      (node (ref "U$20") (pin "P$5") (pinfunction "D_P$5") (pintype "passive"))
      (node (ref "U$20") (pin "P$6") (pinfunction "D_P$6") (pintype "passive"))
      (node (ref "U$20") (pin "P$7") (pinfunction "D_P$7") (pintype "passive"))
      (node (ref "U$20") (pin "P$8") (pinfunction "D_P$8") (pintype "passive"))
      (node (ref "U$23") (pin "13") (pinfunction "K_13") (pintype "passive"))
    )
    (net (code "91") (name "Net-(U$23G-K)") (class "Default")
      (node (ref "U$22") (pin "P$5") (pinfunction "D_P$5") (pintype "passive"))
      (node (ref "U$22") (pin "P$6") (pinfunction "D_P$6") (pintype "passive"))
      (node (ref "U$22") (pin "P$7") (pinfunction "D_P$7") (pintype "passive"))
      (node (ref "U$22") (pin "P$8") (pinfunction "D_P$8") (pintype "passive"))
      (node (ref "U$23") (pin "15") (pinfunction "K_15") (pintype "passive"))
    )
    (net (code "92") (name "Net-(U$23I-K)") (class "Default")
      (node (ref "R18") (pin "2") (pinfunction "2_2") (pintype "passive"))
      (node (ref "U$19") (pin "12") (pinfunction "OUT1_12") (pintype "output"))
      (node (ref "U$19") (pin "13") (pinfunction "OUT1_13") (pintype "output"))
      (node (ref "U$19") (pin "14") (pinfunction "OUT1_14") (pintype "output"))
      (node (ref "U$19") (pin "15") (pinfunction "OUT1_15") (pintype "output"))
      (node (ref "U$23") (pin "17") (pinfunction "K_17") (pintype "passive"))
    )
    (net (code "93") (name "Net-(U$23J-K)") (class "Default")
      (node (ref "R19") (pin "2") (pinfunction "2_2") (pintype "passive"))
      (node (ref "U$21") (pin "12") (pinfunction "OUT1_12") (pintype "output"))
      (node (ref "U$21") (pin "13") (pinfunction "OUT1_13") (pintype "output"))
      (node (ref "U$21") (pin "14") (pinfunction "OUT1_14") (pintype "output"))
      (node (ref "U$21") (pin "15") (pinfunction "OUT1_15") (pintype "output"))
      (node (ref "U$23") (pin "18") (pinfunction "K_18") (pintype "passive"))
    )
    (net (code "94") (name "Net-(U$23K-K)") (class "Default")
      (node (ref "LED4") (pin "C") (pinfunction "C_C") (pintype "passive"))
      (node (ref "LED5") (pin "A") (pinfunction "A_A") (pintype "passive"))
      (node (ref "U$19") (pin "27") (pinfunction "OUT2_27") (pintype "output"))
      (node (ref "U$19") (pin "28") (pinfunction "OUT2_28") (pintype "output"))
      (node (ref "U$19") (pin "29") (pinfunction "OUT2_29") (pintype "output"))
      (node (ref "U$19") (pin "30") (pinfunction "OUT2_30") (pintype "output"))
      (node (ref "U$23") (pin "19") (pinfunction "K_19") (pintype "passive"))
    )
    (net (code "95") (name "Net-(U$23L-K)") (class "Default")
      (node (ref "RN8") (pin "1") (pinfunction "1_1") (pintype "passive"))
      (node (ref "U$23") (pin "2") (pinfunction "K_2") (pintype "passive"))
    )
    (net (code "96") (name "Net-(U$23M-K)") (class "Default")
      (node (ref "LED6") (pin "C") (pinfunction "C_C") (pintype "passive"))
      (node (ref "LED7") (pin "A") (pinfunction "A_A") (pintype "passive"))
      (node (ref "U$21") (pin "27") (pinfunction "OUT2_27") (pintype "output"))
      (node (ref "U$21") (pin "28") (pinfunction "OUT2_28") (pintype "output"))
      (node (ref "U$21") (pin "29") (pinfunction "OUT2_29") (pintype "output"))
      (node (ref "U$21") (pin "30") (pinfunction "OUT2_30") (pintype "output"))
      (node (ref "U$23") (pin "20") (pinfunction "K_20") (pintype "passive"))
    )
    (net (code "97") (name "Net-(U$23R-K)") (class "Default")
      (node (ref "U$10") (pin "P$5") (pinfunction "D_P$5") (pintype "passive"))
      (node (ref "U$10") (pin "P$6") (pinfunction "D_P$6") (pintype "passive"))
      (node (ref "U$10") (pin "P$7") (pinfunction "D_P$7") (pintype "passive"))
      (node (ref "U$10") (pin "P$8") (pinfunction "D_P$8") (pintype "passive"))
      (node (ref "U$23") (pin "3") (pinfunction "K_3") (pintype "passive"))
    )
    (net (code "98") (name "Net-(U$23T-K)") (class "Default")
      (node (ref "U$12") (pin "P$5") (pinfunction "D_P$5") (pintype "passive"))
      (node (ref "U$12") (pin "P$6") (pinfunction "D_P$6") (pintype "passive"))
      (node (ref "U$12") (pin "P$7") (pinfunction "D_P$7") (pintype "passive"))
      (node (ref "U$12") (pin "P$8") (pinfunction "D_P$8") (pintype "passive"))
      (node (ref "U$23") (pin "5") (pinfunction "K_5") (pintype "passive"))
    )
    (net (code "99") (name "Net-(U$23V-K)") (class "Default")
      (node (ref "U$14") (pin "P$5") (pinfunction "D_P$5") (pintype "passive"))
      (node (ref "U$14") (pin "P$6") (pinfunction "D_P$6") (pintype "passive"))
      (node (ref "U$14") (pin "P$7") (pinfunction "D_P$7") (pintype "passive"))
      (node (ref "U$14") (pin "P$8") (pinfunction "D_P$8") (pintype "passive"))
      (node (ref "U$23") (pin "7") (pinfunction "K_7") (pintype "passive"))
    )
    (net (code "100") (name "Net-(U$23X-K)") (class "Default")
      (node (ref "U$16") (pin "P$5") (pinfunction "D_P$5") (pintype "passive"))
      (node (ref "U$16") (pin "P$6") (pinfunction "D_P$6") (pintype "passive"))
      (node (ref "U$16") (pin "P$7") (pinfunction "D_P$7") (pintype "passive"))
      (node (ref "U$16") (pin "P$8") (pinfunction "D_P$8") (pintype "passive"))
      (node (ref "U$23") (pin "9") (pinfunction "K_9") (pintype "passive"))
    )
    (net (code "101") (name "unconnected-(LOGO-PadP$1)") (class "Default")
      (node (ref "LOGO") (pin "P$1") (pinfunction "P$1_P$1") (pintype "bidirectional"))
    )
    (net (code "102") (name "unconnected-(LOGOA-P$1-PadP$2)") (class "Default")
      (node (ref "LOGO") (pin "P$2") (pinfunction "P$1_P$2") (pintype "bidirectional"))
    )
    (net (code "103") (name "unconnected-(PCB1-PadP8.3)") (class "Default")
      (node (ref "PCB1") (pin "P8.3") (pinfunction "P8.3_P8.3") (pintype "bidirectional"))
    )
    (net (code "104") (name "unconnected-(PCB1-PadP8.4)") (class "Default")
      (node (ref "PCB1") (pin "P8.4") (pinfunction "P8.4_P8.4") (pintype "bidirectional"))
    )
    (net (code "105") (name "unconnected-(PCB1-PadP8.5)") (class "Default")
      (node (ref "PCB1") (pin "P8.5") (pinfunction "P8.5_P8.5") (pintype "bidirectional"))
    )
    (net (code "106") (name "unconnected-(PCB1-PadP8.6)") (class "Default")
      (node (ref "PCB1") (pin "P8.6") (pinfunction "P8.6_P8.6") (pintype "bidirectional"))
    )
    (net (code "107") (name "unconnected-(PCB1-PadP8.7)") (class "Default")
      (node (ref "PCB1") (pin "P8.7") (pinfunction "P8.7_P8.7") (pintype "bidirectional"))
    )
    (net (code "108") (name "unconnected-(PCB1-PadP8.8)") (class "Default")
      (node (ref "PCB1") (pin "P8.8") (pinfunction "P8.8_P8.8") (pintype "bidirectional"))
    )
    (net (code "109") (name "unconnected-(PCB1-PadP8.9)") (class "Default")
      (node (ref "PCB1") (pin "P8.9") (pinfunction "P8.9_P8.9") (pintype "bidirectional"))
    )
    (net (code "110") (name "unconnected-(PCB1-PadP8.10)") (class "Default")
      (node (ref "PCB1") (pin "P8.10") (pinfunction "P8.10_P8.10") (pintype "bidirectional"))
    )
    (net (code "111") (name "unconnected-(PCB1-PadP8.11)") (class "Default")
      (node (ref "PCB1") (pin "P8.11") (pinfunction "P8.11_P8.11") (pintype "bidirectional"))
    )
    (net (code "112") (name "unconnected-(PCB1-PadP8.12)") (class "Default")
      (node (ref "PCB1") (pin "P8.12") (pinfunction "P8.12_P8.12") (pintype "bidirectional"))
    )
    (net (code "113") (name "unconnected-(PCB1-PadP8.13)") (class "Default")
      (node (ref "PCB1") (pin "P8.13") (pinfunction "P8.13_P8.13") (pintype "bidirectional"))
    )
    (net (code "114") (name "unconnected-(PCB1-PadP8.14)") (class "Default")
      (node (ref "PCB1") (pin "P8.14") (pinfunction "P8.14_P8.14") (pintype "bidirectional"))
    )
    (net (code "115") (name "unconnected-(PCB1-PadP8.15)") (class "Default")
      (node (ref "PCB1") (pin "P8.15") (pinfunction "P8.15_P8.15") (pintype "bidirectional"))
    )
    (net (code "116") (name "unconnected-(PCB1-PadP8.16)") (class "Default")
      (node (ref "PCB1") (pin "P8.16") (pinfunction "P8.16_P8.16") (pintype "bidirectional"))
    )
    (net (code "117") (name "unconnected-(PCB1-PadP8.17)") (class "Default")
      (node (ref "PCB1") (pin "P8.17") (pinfunction "P8.17_P8.17") (pintype "bidirectional"))
    )
    (net (code "118") (name "unconnected-(PCB1-PadP8.18)") (class "Default")
      (node (ref "PCB1") (pin "P8.18") (pinfunction "P8.18_P8.18") (pintype "bidirectional"))
    )
    (net (code "119") (name "unconnected-(PCB1-PadP8.19)") (class "Default")
      (node (ref "PCB1") (pin "P8.19") (pinfunction "P8.19_P8.19") (pintype "bidirectional"))
    )
    (net (code "120") (name "unconnected-(PCB1-PadP8.20)") (class "Default")
      (node (ref "PCB1") (pin "P8.20") (pinfunction "P8.20_P8.20") (pintype "bidirectional"))
    )
    (net (code "121") (name "unconnected-(PCB1-PadP8.21)") (class "Default")
      (node (ref "PCB1") (pin "P8.21") (pinfunction "P8.21_P8.21") (pintype "bidirectional"))
    )
    (net (code "122") (name "unconnected-(PCB1-PadP8.22)") (class "Default")
      (node (ref "PCB1") (pin "P8.22") (pinfunction "P8.22_P8.22") (pintype "bidirectional"))
    )
    (net (code "123") (name "unconnected-(PCB1-PadP8.23)") (class "Default")
      (node (ref "PCB1") (pin "P8.23") (pinfunction "P8.23_P8.23") (pintype "bidirectional"))
    )
    (net (code "124") (name "unconnected-(PCB1-PadP8.24)") (class "Default")
      (node (ref "PCB1") (pin "P8.24") (pinfunction "P8.24_P8.24") (pintype "bidirectional"))
    )
    (net (code "125") (name "unconnected-(PCB1-PadP8.25)") (class "Default")
      (node (ref "PCB1") (pin "P8.25") (pinfunction "P8.25_P8.25") (pintype "bidirectional"))
    )
    (net (code "126") (name "unconnected-(PCB1-PadP8.26)") (class "Default")
      (node (ref "PCB1") (pin "P8.26") (pinfunction "P8.26_P8.26") (pintype "bidirectional"))
    )
    (net (code "127") (name "unconnected-(PCB1-PadP8.27)") (class "Default")
      (node (ref "PCB1") (pin "P8.27") (pinfunction "P8.27_P8.27") (pintype "bidirectional"))
    )
    (net (code "128") (name "unconnected-(PCB1-PadP8.28)") (class "Default")
      (node (ref "PCB1") (pin "P8.28") (pinfunction "P8.28_P8.28") (pintype "bidirectional"))
    )
    (net (code "129") (name "unconnected-(PCB1-PadP8.29)") (class "Default")
      (node (ref "PCB1") (pin "P8.29") (pinfunction "P8.29_P8.29") (pintype "bidirectional"))
    )
    (net (code "130") (name "unconnected-(PCB1-PadP8.30)") (class "Default")
      (node (ref "PCB1") (pin "P8.30") (pinfunction "P8.30_P8.30") (pintype "bidirectional"))
    )
    (net (code "131") (name "unconnected-(PCB1-PadP8.31)") (class "Default")
      (node (ref "PCB1") (pin "P8.31") (pinfunction "P8.31_P8.31") (pintype "bidirectional"))
    )
    (net (code "132") (name "unconnected-(PCB1-PadP8.32)") (class "Default")
      (node (ref "PCB1") (pin "P8.32") (pinfunction "P8.32_P8.32") (pintype "bidirectional"))
    )
    (net (code "133") (name "unconnected-(PCB1-PadP8.33)") (class "Default")
      (node (ref "PCB1") (pin "P8.33") (pinfunction "P8.33_P8.33") (pintype "bidirectional"))
    )
    (net (code "134") (name "unconnected-(PCB1-PadP8.34)") (class "Default")
      (node (ref "PCB1") (pin "P8.34") (pinfunction "P8.34_P8.34") (pintype "bidirectional"))
    )
    (net (code "135") (name "unconnected-(PCB1-PadP8.35)") (class "Default")
      (node (ref "PCB1") (pin "P8.35") (pinfunction "P8.35_P8.35") (pintype "bidirectional"))
    )
    (net (code "136") (name "unconnected-(PCB1-PadP8.36)") (class "Default")
      (node (ref "PCB1") (pin "P8.36") (pinfunction "P8.36_P8.36") (pintype "bidirectional"))
    )
    (net (code "137") (name "unconnected-(PCB1-PadP8.37)") (class "Default")
      (node (ref "PCB1") (pin "P8.37") (pinfunction "P8.37_P8.37") (pintype "bidirectional"))
    )
    (net (code "138") (name "unconnected-(PCB1-PadP8.38)") (class "Default")
      (node (ref "PCB1") (pin "P8.38") (pinfunction "P8.38_P8.38") (pintype "bidirectional"))
    )
    (net (code "139") (name "unconnected-(PCB1-PadP8.39)") (class "Default")
      (node (ref "PCB1") (pin "P8.39") (pinfunction "P8.39_P8.39") (pintype "bidirectional"))
    )
    (net (code "140") (name "unconnected-(PCB1-PadP8.40)") (class "Default")
      (node (ref "PCB1") (pin "P8.40") (pinfunction "P8.40_P8.40") (pintype "bidirectional"))
    )
    (net (code "141") (name "unconnected-(PCB1-PadP8.41)") (class "Default")
      (node (ref "PCB1") (pin "P8.41") (pinfunction "P8.41_P8.41") (pintype "bidirectional"))
    )
    (net (code "142") (name "unconnected-(PCB1-PadP8.42)") (class "Default")
      (node (ref "PCB1") (pin "P8.42") (pinfunction "P8.42_P8.42") (pintype "bidirectional"))
    )
    (net (code "143") (name "unconnected-(PCB1-PadP8.43)") (class "Default")
      (node (ref "PCB1") (pin "P8.43") (pinfunction "P8.43_P8.43") (pintype "bidirectional"))
    )
    (net (code "144") (name "unconnected-(PCB1-PadP8.44)") (class "Default")
      (node (ref "PCB1") (pin "P8.44") (pinfunction "P8.44_P8.44") (pintype "bidirectional"))
    )
    (net (code "145") (name "unconnected-(PCB1-PadP8.45)") (class "Default")
      (node (ref "PCB1") (pin "P8.45") (pinfunction "P8.45_P8.45") (pintype "bidirectional"))
    )
    (net (code "146") (name "unconnected-(PCB1-PadP8.46)") (class "Default")
      (node (ref "PCB1") (pin "P8.46") (pinfunction "P8.46_P8.46") (pintype "bidirectional"))
    )
    (net (code "147") (name "unconnected-(PCB1-PadP9.3)") (class "Default")
      (node (ref "PCB1") (pin "P9.3") (pinfunction "P9.3_P9.3") (pintype "bidirectional"))
    )
    (net (code "148") (name "unconnected-(PCB1-PadP9.4)") (class "Default")
      (node (ref "PCB1") (pin "P9.4") (pinfunction "P9.4_P9.4") (pintype "bidirectional"))
    )
    (net (code "149") (name "unconnected-(PCB1-PadP9.7)") (class "Default")
      (node (ref "PCB1") (pin "P9.7") (pinfunction "P9.7_P9.7") (pintype "bidirectional"))
    )
    (net (code "150") (name "unconnected-(PCB1-PadP9.8)") (class "Default")
      (node (ref "PCB1") (pin "P9.8") (pinfunction "P9.8_P9.8") (pintype "bidirectional"))
    )
    (net (code "151") (name "unconnected-(PCB1-PadP9.9)") (class "Default")
      (node (ref "PCB1") (pin "P9.9") (pinfunction "P9.9_P9.9") (pintype "bidirectional"))
    )
    (net (code "152") (name "unconnected-(PCB1-PadP9.10)") (class "Default")
      (node (ref "PCB1") (pin "P9.10") (pinfunction "P9.10_P9.10") (pintype "bidirectional"))
    )
    (net (code "153") (name "unconnected-(PCB1-PadP9.11)") (class "Default")
      (node (ref "PCB1") (pin "P9.11") (pinfunction "P9.11_P9.11") (pintype "bidirectional"))
    )
    (net (code "154") (name "unconnected-(PCB1-PadP9.12)") (class "Default")
      (node (ref "PCB1") (pin "P9.12") (pinfunction "P9.12_P9.12") (pintype "bidirectional"))
    )
    (net (code "155") (name "unconnected-(PCB1-PadP9.13)") (class "Default")
      (node (ref "PCB1") (pin "P9.13") (pinfunction "P9.13_P9.13") (pintype "bidirectional"))
    )
    (net (code "156") (name "unconnected-(PCB1-PadP9.14)") (class "Default")
      (node (ref "PCB1") (pin "P9.14") (pinfunction "P9.14_P9.14") (pintype "bidirectional"))
    )
    (net (code "157") (name "unconnected-(PCB1-PadP9.15)") (class "Default")
      (node (ref "PCB1") (pin "P9.15") (pinfunction "P9.15_P9.15") (pintype "bidirectional"))
    )
    (net (code "158") (name "unconnected-(PCB1-PadP9.16)") (class "Default")
      (node (ref "PCB1") (pin "P9.16") (pinfunction "P9.16_P9.16") (pintype "bidirectional"))
    )
    (net (code "159") (name "unconnected-(PCB1-PadP9.17)") (class "Default")
      (node (ref "PCB1") (pin "P9.17") (pinfunction "P9.17_P9.17") (pintype "bidirectional"))
    )
    (net (code "160") (name "unconnected-(PCB1-PadP9.18)") (class "Default")
      (node (ref "PCB1") (pin "P9.18") (pinfunction "P9.18_P9.18") (pintype "bidirectional"))
    )
    (net (code "161") (name "unconnected-(PCB1-PadP9.19)") (class "Default")
      (node (ref "PCB1") (pin "P9.19") (pinfunction "P9.19_P9.19") (pintype "bidirectional"))
    )
    (net (code "162") (name "unconnected-(PCB1-PadP9.20)") (class "Default")
      (node (ref "PCB1") (pin "P9.20") (pinfunction "P9.20_P9.20") (pintype "bidirectional"))
    )
    (net (code "163") (name "unconnected-(PCB1-PadP9.21)") (class "Default")
      (node (ref "PCB1") (pin "P9.21") (pinfunction "P9.21_P9.21") (pintype "bidirectional"))
    )
    (net (code "164") (name "unconnected-(PCB1-PadP9.22)") (class "Default")
      (node (ref "PCB1") (pin "P9.22") (pinfunction "P9.22_P9.22") (pintype "bidirectional"))
    )
    (net (code "165") (name "unconnected-(PCB1-PadP9.23)") (class "Default")
      (node (ref "PCB1") (pin "P9.23") (pinfunction "P9.23_P9.23") (pintype "bidirectional"))
    )
    (net (code "166") (name "unconnected-(PCB1-PadP9.29)") (class "Default")
      (node (ref "PCB1") (pin "P9.29") (pinfunction "P9.29_P9.29") (pintype "bidirectional"))
    )
    (net (code "167") (name "unconnected-(PCB1-PadP9.30)") (class "Default")
      (node (ref "PCB1") (pin "P9.30") (pinfunction "P9.30_P9.30") (pintype "bidirectional"))
    )
    (net (code "168") (name "unconnected-(PCB1-PadP9.31)") (class "Default")
      (node (ref "PCB1") (pin "P9.31") (pinfunction "P9.31_P9.31") (pintype "bidirectional"))
    )
    (net (code "169") (name "unconnected-(PCB1-PadP9.32)") (class "Default")
      (node (ref "PCB1") (pin "P9.32") (pinfunction "P9.32_P9.32") (pintype "bidirectional"))
    )
    (net (code "170") (name "unconnected-(PCB1-PadP9.33)") (class "Default")
      (node (ref "PCB1") (pin "P9.33") (pinfunction "P9.33_P9.33") (pintype "bidirectional"))
    )
    (net (code "171") (name "unconnected-(PCB1-PadP9.34)") (class "Default")
      (node (ref "PCB1") (pin "P9.34") (pinfunction "P9.34_P9.34") (pintype "bidirectional"))
    )
    (net (code "172") (name "unconnected-(PCB1-PadP9.35)") (class "Default")
      (node (ref "PCB1") (pin "P9.35") (pinfunction "P9.35_P9.35") (pintype "bidirectional"))
    )
    (net (code "173") (name "unconnected-(PCB1-PadP9.36)") (class "Default")
      (node (ref "PCB1") (pin "P9.36") (pinfunction "P9.36_P9.36") (pintype "bidirectional"))
    )
    (net (code "174") (name "unconnected-(PCB1-PadP9.37)") (class "Default")
      (node (ref "PCB1") (pin "P9.37") (pinfunction "P9.37_P9.37") (pintype "bidirectional"))
    )
    (net (code "175") (name "unconnected-(PCB1-PadP9.38)") (class "Default")
      (node (ref "PCB1") (pin "P9.38") (pinfunction "P9.38_P9.38") (pintype "bidirectional"))
    )
    (net (code "176") (name "unconnected-(PCB1-PadP9.39)") (class "Default")
      (node (ref "PCB1") (pin "P9.39") (pinfunction "P9.39_P9.39") (pintype "bidirectional"))
    )
    (net (code "177") (name "unconnected-(PCB1-PadP9.40)") (class "Default")
      (node (ref "PCB1") (pin "P9.40") (pinfunction "P9.40_P9.40") (pintype "bidirectional"))
    )
    (net (code "178") (name "unconnected-(PCB1-PadP9.41)") (class "Default")
      (node (ref "PCB1") (pin "P9.41") (pinfunction "P9.41_P9.41") (pintype "bidirectional"))
    )
    (net (code "179") (name "unconnected-(PCB1-PadP9.42)") (class "Default")
      (node (ref "PCB1") (pin "P9.42") (pinfunction "P9.42_P9.42") (pintype "bidirectional"))
    )
    (net (code "180") (name "unconnected-(U$13-INT-Pad8)") (class "Default")
      (node (ref "U$13") (pin "8") (pinfunction "INT_8") (pintype "output"))
    )
    (net (code "181") (name "unconnected-(U$17-INT-Pad8)") (class "Default")
      (node (ref "U$17") (pin "8") (pinfunction "INT_8") (pintype "output"))
    )
  )
)
